# BreakoutBoard.net
KiCad netlist of a schematic drawn in EAGLE
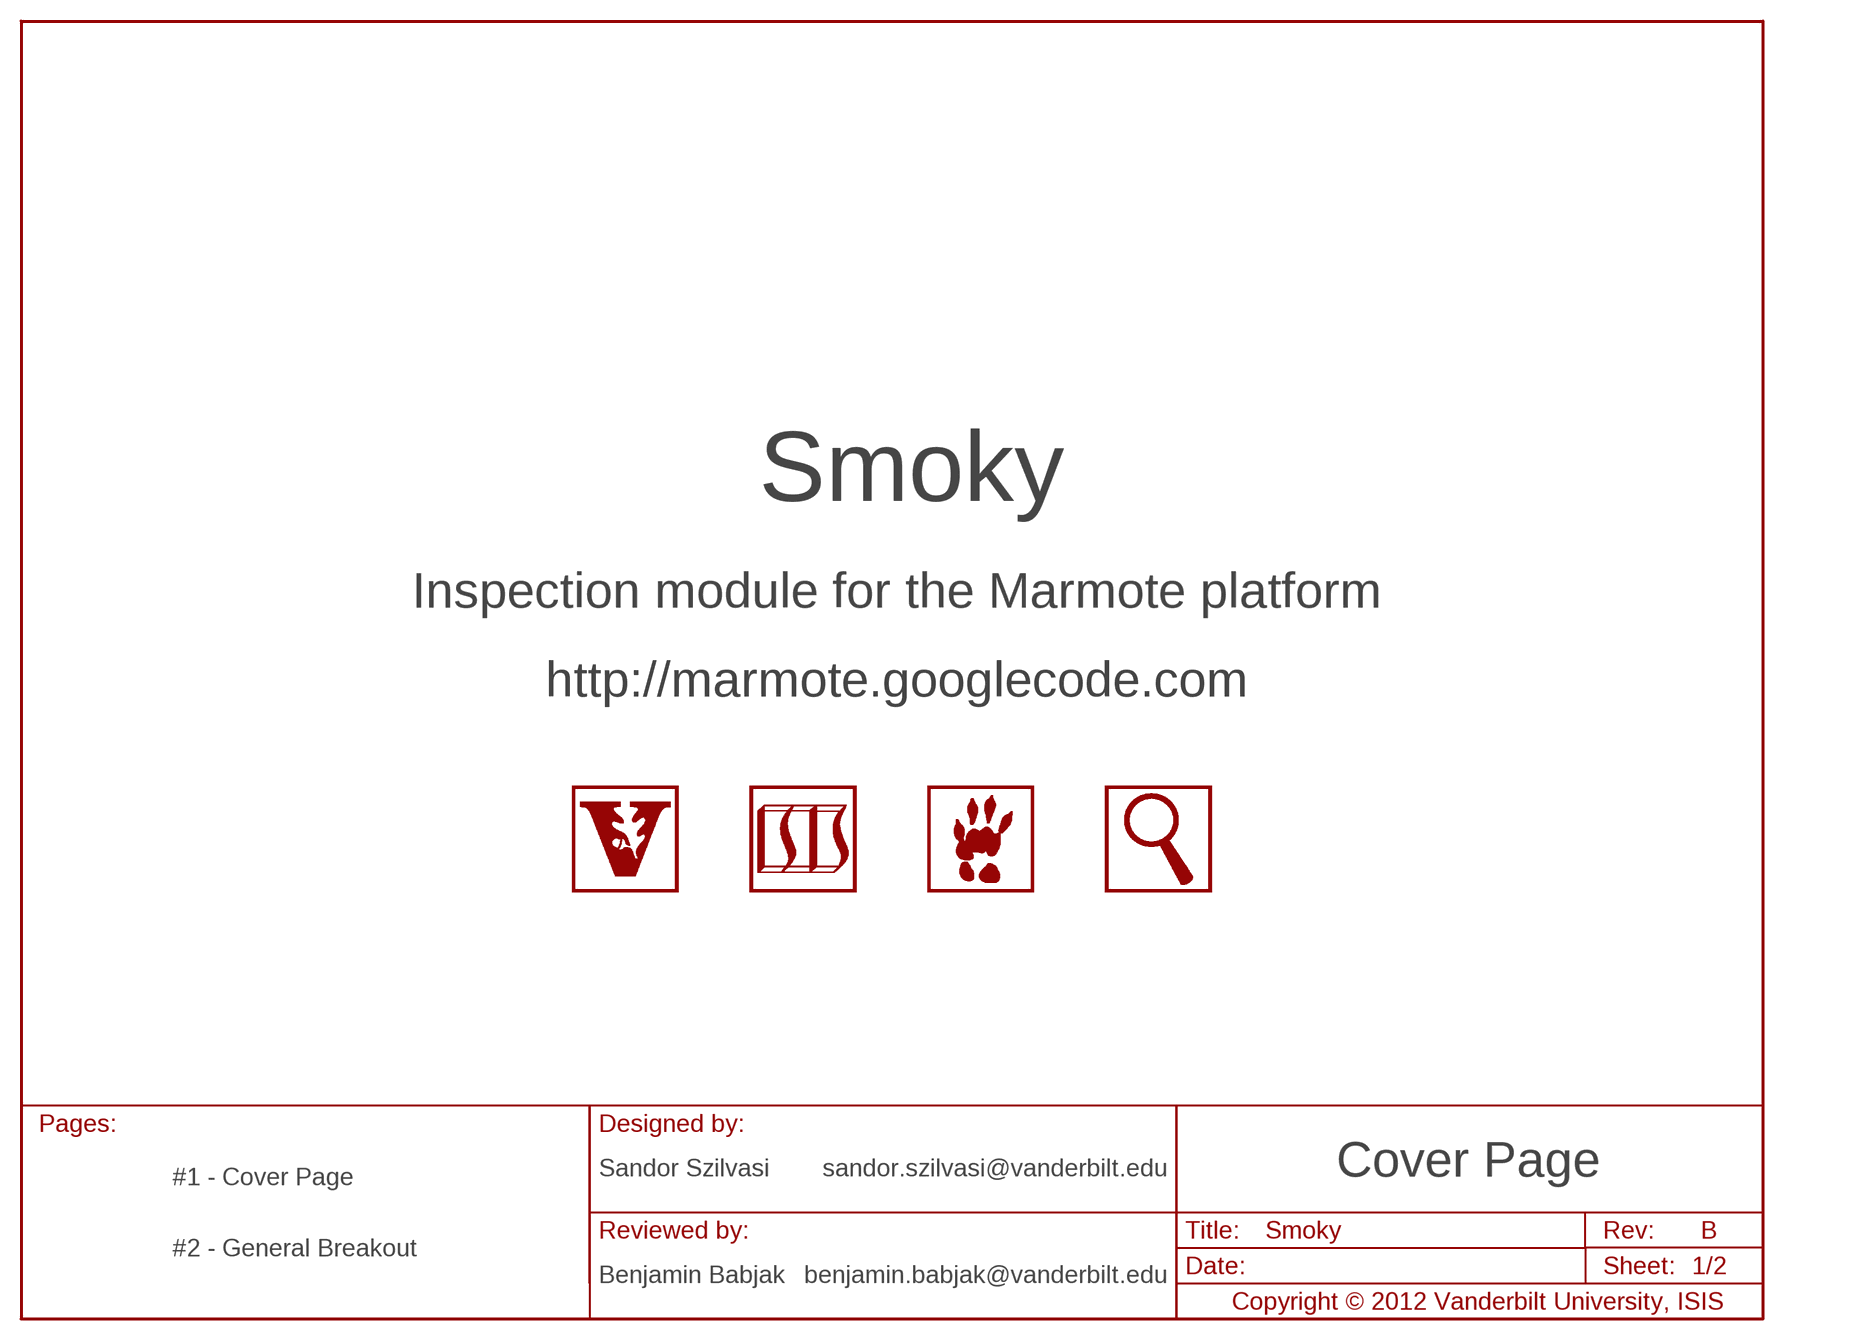
[diagram p0: schematic, sheet 1]
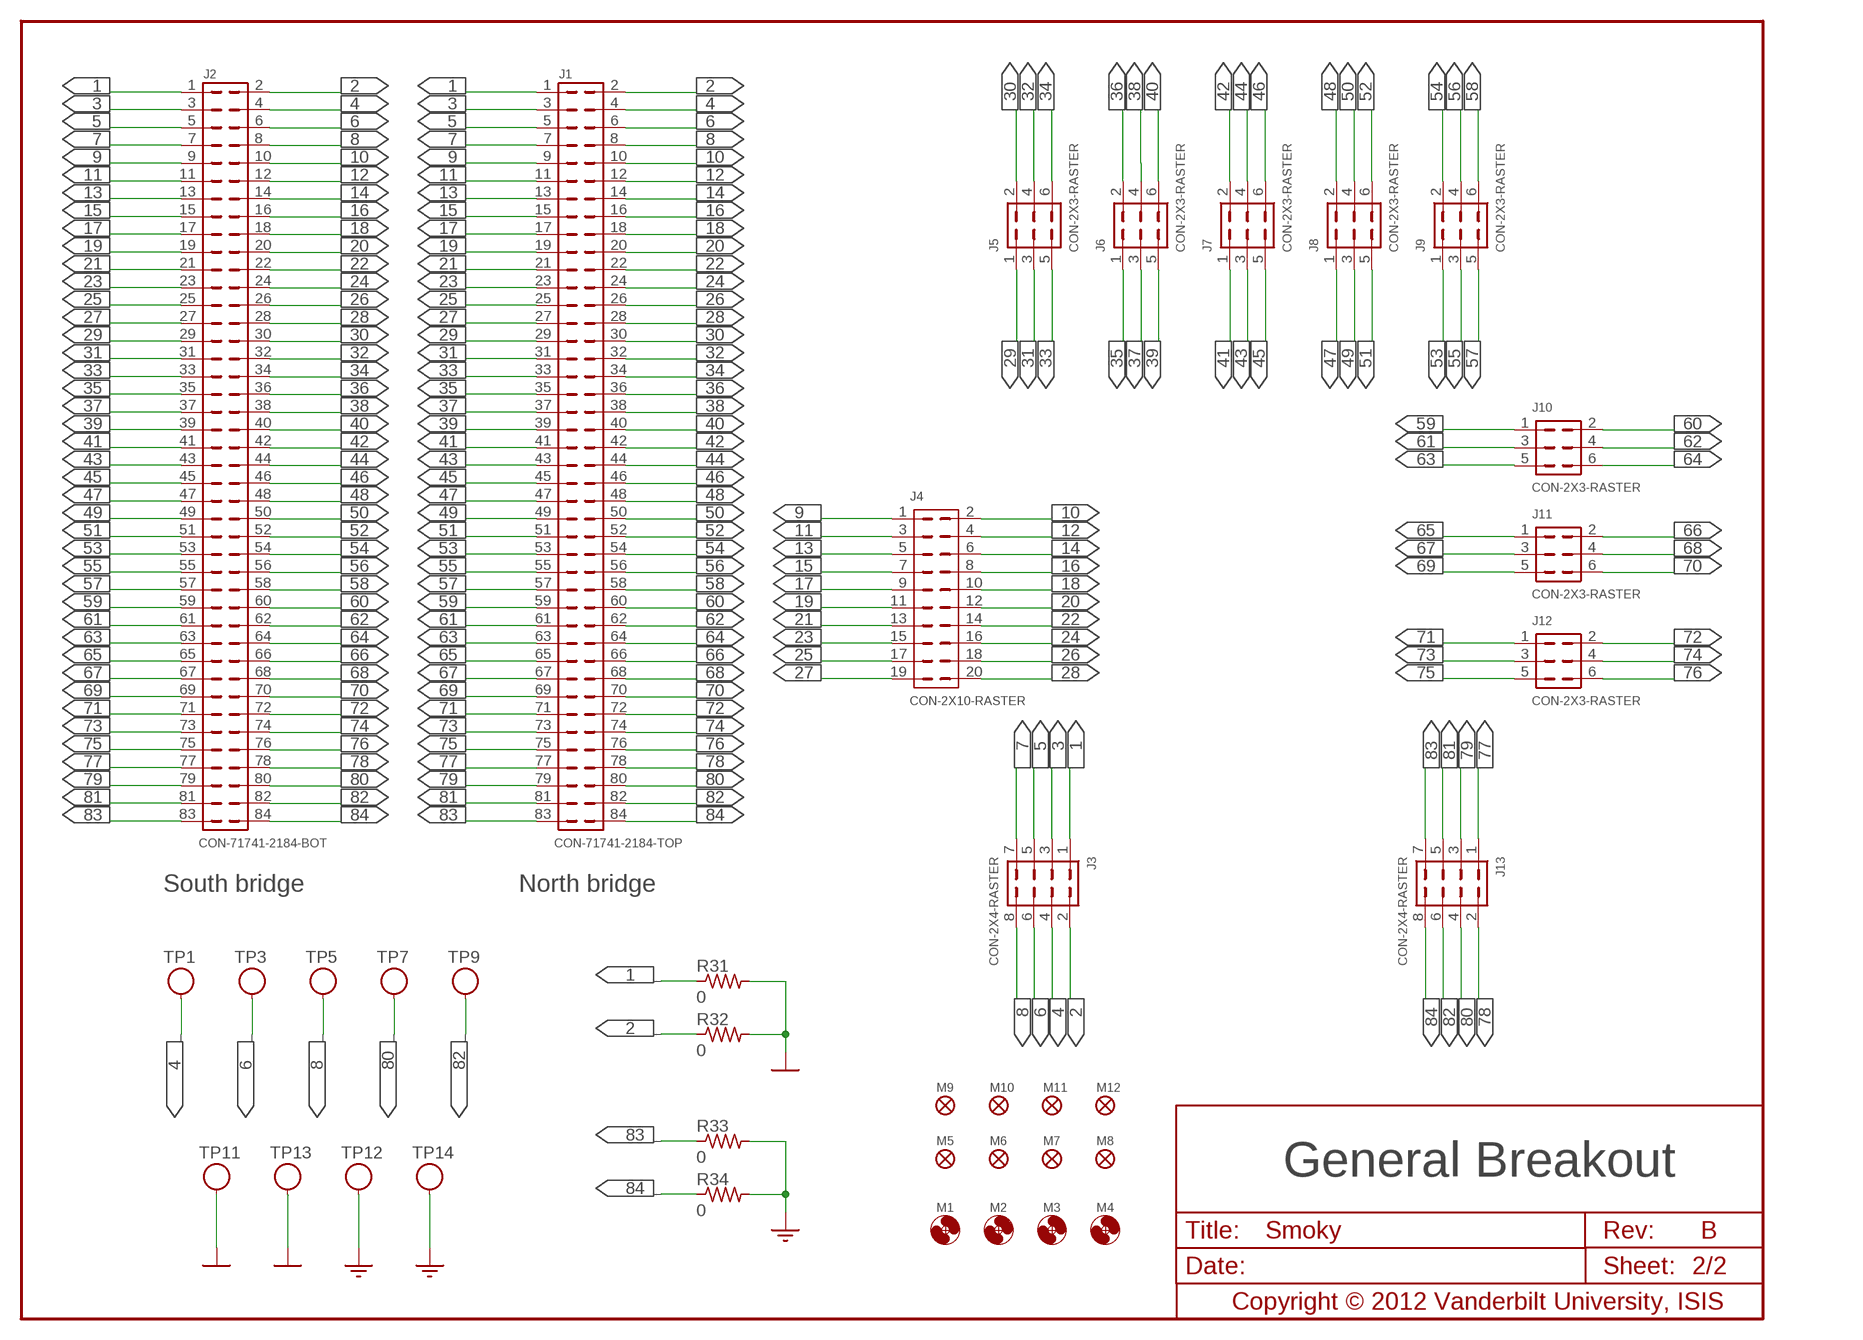
[diagram p1: schematic, sheet 2]

(export (version "E")
  (design (tool "Eeschema 10.0.6"))
  (components
    (comp (ref "J1")
      (value "CON-71741-2184-TOP")
      (footprint "eagle-import:71741-0002")
      (fields (field (name "MF") "Molex") (field (name "MPN") "71741-0002"))
      (libsource (lib "eagle-import") (part "CON-7174184-TOP-21"))
    )
    (comp (ref "J2")
      (value "CON-71741-2184-BOT")
      (footprint "eagle-import:71742-3003-BOT")
      (fields (field (name "MF") "Molex") (field (name "MPN") "71742-3003"))
      (libsource (lib "eagle-import") (part "CON-7174184-BOT-21"))
    )
    (comp (ref "J3")
      (value "CON-2X4-RASTER")
      (footprint "eagle-import:2X8")
      (libsource (lib "eagle-import") (part "CON-2X4-RASTER"))
    )
    (comp (ref "J4")
      (value "CON-2X10-RASTER")
      (footprint "eagle-import:2X20")
      (libsource (lib "eagle-import") (part "CON-2X10-RASTER"))
    )
    (comp (ref "J5")
      (value "CON-2X3-RASTER")
      (footprint "eagle-import:2X6")
      (libsource (lib "eagle-import") (part "CON-2X3-RASTER"))
    )
    (comp (ref "J6")
      (value "CON-2X3-RASTER")
      (footprint "eagle-import:2X6")
      (libsource (lib "eagle-import") (part "CON-2X3-RASTER"))
    )
    (comp (ref "J7")
      (value "CON-2X3-RASTER")
      (footprint "eagle-import:2X6")
      (libsource (lib "eagle-import") (part "CON-2X3-RASTER"))
    )
    (comp (ref "J8")
      (value "CON-2X3-RASTER")
      (footprint "eagle-import:2X6")
      (libsource (lib "eagle-import") (part "CON-2X3-RASTER"))
    )
    (comp (ref "J9")
      (value "CON-2X3-RASTER")
      (footprint "eagle-import:2X6")
      (libsource (lib "eagle-import") (part "CON-2X3-RASTER"))
    )
    (comp (ref "J10")
      (value "CON-2X3-RASTER")
      (footprint "eagle-import:2X6")
      (libsource (lib "eagle-import") (part "CON-2X3-RASTER"))
    )
    (comp (ref "J11")
      (value "CON-2X3-RASTER")
      (footprint "eagle-import:2X6")
      (libsource (lib "eagle-import") (part "CON-2X3-RASTER"))
    )
    (comp (ref "J12")
      (value "CON-2X3-RASTER")
      (footprint "eagle-import:2X6")
      (libsource (lib "eagle-import") (part "CON-2X3-RASTER"))
    )
    (comp (ref "J13")
      (value "CON-2X4-RASTER")
      (footprint "eagle-import:2X8")
      (libsource (lib "eagle-import") (part "CON-2X4-RASTER"))
    )
    (comp (ref "M1")
      (value "MOUNT-HOLE3.3")
      (footprint "eagle-import:3,3")
      (libsource (lib "eagle-import") (part "MOUNT-HOLE3.3"))
    )
    (comp (ref "M2")
      (value "MOUNT-HOLE3.3")
      (footprint "eagle-import:3,3")
      (libsource (lib "eagle-import") (part "MOUNT-HOLE3.3"))
    )
    (comp (ref "M3")
      (value "MOUNT-HOLE3.3")
      (footprint "eagle-import:3,3")
      (libsource (lib "eagle-import") (part "MOUNT-HOLE3.3"))
    )
    (comp (ref "M4")
      (value "MOUNT-HOLE3.3")
      (footprint "eagle-import:3,3")
      (libsource (lib "eagle-import") (part "MOUNT-HOLE3.3"))
    )
    (comp (ref "M5")
      (value "FIDUCIAL1X2")
      (footprint "eagle-import:FIDUCIAL-1X2")
      (libsource (lib "eagle-import") (part "FIDUCIAL1X2"))
    )
    (comp (ref "M6")
      (value "FIDUCIAL1X2")
      (footprint "eagle-import:FIDUCIAL-1X2")
      (libsource (lib "eagle-import") (part "FIDUCIAL1X2"))
    )
    (comp (ref "M7")
      (value "FIDUCIAL1X2")
      (footprint "eagle-import:FIDUCIAL-1X2")
      (libsource (lib "eagle-import") (part "FIDUCIAL1X2"))
    )
    (comp (ref "M8")
      (value "FIDUCIAL1X2")
      (footprint "eagle-import:FIDUCIAL-1X2")
      (libsource (lib "eagle-import") (part "FIDUCIAL1X2"))
    )
    (comp (ref "M9")
      (value "FIDUCIAL1X2")
      (footprint "eagle-import:FIDUCIAL-1X2")
      (libsource (lib "eagle-import") (part "FIDUCIAL1X2"))
    )
    (comp (ref "M10")
      (value "FIDUCIAL1X2")
      (footprint "eagle-import:FIDUCIAL-1X2")
      (libsource (lib "eagle-import") (part "FIDUCIAL1X2"))
    )
    (comp (ref "M11")
      (value "FIDUCIAL1X2")
      (footprint "eagle-import:FIDUCIAL-1X2")
      (libsource (lib "eagle-import") (part "FIDUCIAL1X2"))
    )
    (comp (ref "M12")
      (value "FIDUCIAL1X2")
      (footprint "eagle-import:FIDUCIAL-1X2")
      (libsource (lib "eagle-import") (part "FIDUCIAL1X2"))
    )
    (comp (ref "R31")
      (value "0")
      (footprint "eagle-import:R0805")
      (libsource (lib "eagle-import") (part "R0805"))
    )
    (comp (ref "R32")
      (value "0")
      (footprint "eagle-import:R0805")
      (libsource (lib "eagle-import") (part "R0805"))
    )
    (comp (ref "R33")
      (value "0")
      (footprint "eagle-import:R0805")
      (libsource (lib "eagle-import") (part "R0805"))
    )
    (comp (ref "R34")
      (value "0")
      (footprint "eagle-import:R0805")
      (libsource (lib "eagle-import") (part "R0805"))
    )
    (comp (ref "TP1")
      (value "TESTPOINT-BLUE")
      (footprint "eagle-import:TESTPOINT")
      (fields (field (name "MF") "Keystone") (field (name "MPN") "5122"))
      (libsource (lib "eagle-import") (part "TESTPOINT-BLUE"))
    )
    (comp (ref "TP3")
      (value "TESTPOINT-BLUE")
      (footprint "eagle-import:TESTPOINT")
      (fields (field (name "MF") "Keystone") (field (name "MPN") "5122"))
      (libsource (lib "eagle-import") (part "TESTPOINT-BLUE"))
    )
    (comp (ref "TP5")
      (value "TESTPOINT-BLUE")
      (footprint "eagle-import:TESTPOINT")
      (fields (field (name "MF") "Keystone") (field (name "MPN") "5122"))
      (libsource (lib "eagle-import") (part "TESTPOINT-BLUE"))
    )
    (comp (ref "TP7")
      (value "TESTPOINT-GREEN")
      (footprint "eagle-import:TESTPOINT")
      (fields (field (name "MF") "Keystone") (field (name "MPN") "5121"))
      (libsource (lib "eagle-import") (part "TESTPOINT-GREEN"))
    )
    (comp (ref "TP9")
      (value "TESTPOINT-GREEN")
      (footprint "eagle-import:TESTPOINT")
      (fields (field (name "MF") "Keystone") (field (name "MPN") "5121"))
      (libsource (lib "eagle-import") (part "TESTPOINT-GREEN"))
    )
    (comp (ref "TP11")
      (value "TESTPOINT-YELLOW")
      (footprint "eagle-import:TESTPOINT")
      (fields (field (name "MF") "Keystone") (field (name "MPN") "5009"))
      (libsource (lib "eagle-import") (part "TESTPOINT-YELLOW"))
    )
    (comp (ref "TP12")
      (value "TESTPOINT-YELLOW")
      (footprint "eagle-import:TESTPOINT")
      (fields (field (name "MF") "Keystone") (field (name "MPN") "5009"))
      (libsource (lib "eagle-import") (part "TESTPOINT-YELLOW"))
    )
    (comp (ref "TP13")
      (value "TESTPOINT-YELLOW")
      (footprint "eagle-import:TESTPOINT")
      (fields (field (name "MF") "Keystone") (field (name "MPN") "5009"))
      (libsource (lib "eagle-import") (part "TESTPOINT-YELLOW"))
    )
    (comp (ref "TP14")
      (value "TESTPOINT-YELLOW")
      (footprint "eagle-import:TESTPOINT")
      (fields (field (name "MF") "Keystone") (field (name "MPN") "5009"))
      (libsource (lib "eagle-import") (part "TESTPOINT-YELLOW"))
    )
    (comp (ref "LOGO1")
      (value "LOGO-MAGNIFYING-GLASS-600MIL-10MM-SS")
      (footprint "eagle-import:LOGO-MAGNIFYING-GLASS-10MM-SILKSCREEN")
      (libsource (lib "eagle-import") (part "LOGO-MAGNIFYING-GLASS-600MIL-10MM-SS"))
    )
    (comp (ref "LOGO5")
      (value "LOGO-VANDERBILT-600MIL-10MM-SS")
      (footprint "eagle-import:LOGO-VANDERBILT-10MM-SILKSCREEN")
      (libsource (lib "eagle-import") (part "LOGO-VANDERBILT-600MIL-10MM-SS"))
    )
    (comp (ref "LOGO6")
      (value "LOGO-ISIS-600MIL-10MM-SS")
      (footprint "eagle-import:LOGO-ISIS-10MM-SILKSCREEN")
      (libsource (lib "eagle-import") (part "LOGO-ISIS-600MIL-10MM-SS"))
    )
    (comp (ref "LOGO7")
      (value "LOGO-MARMOTE-600MIL-10MM-SS")
      (footprint "eagle-import:LOGO-MARMOTE-10MM-SILKSCREEN")
      (libsource (lib "eagle-import") (part "LOGO-MARMOTE-600MIL-10MM-SS"))
    )
  )
  (nets
    (net (code "1") (name "1") (class "Default")
      (node (ref "J1") (pin "1") (pinfunction "1_1") (pintype "passive"))
      (node (ref "J2") (pin "1") (pinfunction "1_1") (pintype "passive"))
      (node (ref "J3") (pin "1") (pinfunction "1_1") (pintype "passive"))
      (node (ref "R31") (pin "1") (pinfunction "1_1") (pintype "passive"))
    )
    (net (code "2") (name "2") (class "Default")
      (node (ref "J1") (pin "2") (pinfunction "2_2") (pintype "passive"))
      (node (ref "J2") (pin "2") (pinfunction "2_2") (pintype "passive"))
      (node (ref "J3") (pin "2") (pinfunction "2_2") (pintype "passive"))
      (node (ref "R32") (pin "1") (pinfunction "1_1") (pintype "passive"))
    )
    (net (code "3") (name "3") (class "Default")
      (node (ref "J1") (pin "3") (pinfunction "3_3") (pintype "passive"))
      (node (ref "J2") (pin "3") (pinfunction "3_3") (pintype "passive"))
      (node (ref "J3") (pin "3") (pinfunction "3_3") (pintype "passive"))
    )
    (net (code "4") (name "4") (class "Default")
      (node (ref "J1") (pin "4") (pinfunction "4_4") (pintype "passive"))
      (node (ref "J2") (pin "4") (pinfunction "4_4") (pintype "passive"))
      (node (ref "J3") (pin "4") (pinfunction "4_4") (pintype "passive"))
      (node (ref "TP1") (pin "1") (pinfunction "1_1") (pintype "power_in"))
    )
    (net (code "5") (name "5") (class "Default")
      (node (ref "J1") (pin "5") (pinfunction "5_5") (pintype "passive"))
      (node (ref "J2") (pin "5") (pinfunction "5_5") (pintype "passive"))
      (node (ref "J3") (pin "5") (pinfunction "5_5") (pintype "passive"))
    )
    (net (code "6") (name "6") (class "Default")
      (node (ref "J1") (pin "6") (pinfunction "6_6") (pintype "passive"))
      (node (ref "J2") (pin "6") (pinfunction "6_6") (pintype "passive"))
      (node (ref "J3") (pin "6") (pinfunction "6_6") (pintype "passive"))
      (node (ref "TP3") (pin "1") (pinfunction "1_1") (pintype "power_in"))
    )
    (net (code "7") (name "7") (class "Default")
      (node (ref "J1") (pin "7") (pinfunction "7_7") (pintype "passive"))
      (node (ref "J2") (pin "7") (pinfunction "7_7") (pintype "passive"))
      (node (ref "J3") (pin "7") (pinfunction "7_7") (pintype "passive"))
    )
    (net (code "8") (name "8") (class "Default")
      (node (ref "J1") (pin "8") (pinfunction "8_8") (pintype "passive"))
      (node (ref "J2") (pin "8") (pinfunction "8_8") (pintype "passive"))
      (node (ref "J3") (pin "8") (pinfunction "8_8") (pintype "passive"))
      (node (ref "TP5") (pin "1") (pinfunction "1_1") (pintype "power_in"))
    )
    (net (code "9") (name "9") (class "Default")
      (node (ref "J1") (pin "9") (pinfunction "9_9") (pintype "passive"))
      (node (ref "J2") (pin "9") (pinfunction "9_9") (pintype "passive"))
      (node (ref "J4") (pin "1") (pinfunction "1_1") (pintype "passive"))
    )
    (net (code "10") (name "10") (class "Default")
      (node (ref "J1") (pin "10") (pinfunction "10_10") (pintype "passive"))
      (node (ref "J2") (pin "10") (pinfunction "10_10") (pintype "passive"))
      (node (ref "J4") (pin "2") (pinfunction "2_2") (pintype "passive"))
    )
    (net (code "11") (name "11") (class "Default")
      (node (ref "J1") (pin "11") (pinfunction "11_11") (pintype "passive"))
      (node (ref "J2") (pin "11") (pinfunction "11_11") (pintype "passive"))
      (node (ref "J4") (pin "3") (pinfunction "3_3") (pintype "passive"))
    )
    (net (code "12") (name "12") (class "Default")
      (node (ref "J1") (pin "12") (pinfunction "12_12") (pintype "passive"))
      (node (ref "J2") (pin "12") (pinfunction "12_12") (pintype "passive"))
      (node (ref "J4") (pin "4") (pinfunction "4_4") (pintype "passive"))
    )
    (net (code "13") (name "13") (class "Default")
      (node (ref "J1") (pin "13") (pinfunction "13_13") (pintype "passive"))
      (node (ref "J2") (pin "13") (pinfunction "13_13") (pintype "passive"))
      (node (ref "J4") (pin "5") (pinfunction "5_5") (pintype "passive"))
    )
    (net (code "14") (name "14") (class "Default")
      (node (ref "J1") (pin "14") (pinfunction "14_14") (pintype "passive"))
      (node (ref "J2") (pin "14") (pinfunction "14_14") (pintype "passive"))
      (node (ref "J4") (pin "6") (pinfunction "6_6") (pintype "passive"))
    )
    (net (code "15") (name "15") (class "Default")
      (node (ref "J1") (pin "15") (pinfunction "15_15") (pintype "passive"))
      (node (ref "J2") (pin "15") (pinfunction "15_15") (pintype "passive"))
      (node (ref "J4") (pin "7") (pinfunction "7_7") (pintype "passive"))
    )
    (net (code "16") (name "16") (class "Default")
      (node (ref "J1") (pin "16") (pinfunction "16_16") (pintype "passive"))
      (node (ref "J2") (pin "16") (pinfunction "16_16") (pintype "passive"))
      (node (ref "J4") (pin "8") (pinfunction "8_8") (pintype "passive"))
    )
    (net (code "17") (name "17") (class "Default")
      (node (ref "J1") (pin "17") (pinfunction "17_17") (pintype "passive"))
      (node (ref "J2") (pin "17") (pinfunction "17_17") (pintype "passive"))
      (node (ref "J4") (pin "9") (pinfunction "9_9") (pintype "passive"))
    )
    (net (code "18") (name "18") (class "Default")
      (node (ref "J1") (pin "18") (pinfunction "18_18") (pintype "passive"))
      (node (ref "J2") (pin "18") (pinfunction "18_18") (pintype "passive"))
      (node (ref "J4") (pin "10") (pinfunction "10_10") (pintype "passive"))
    )
    (net (code "19") (name "19") (class "Default")
      (node (ref "J1") (pin "19") (pinfunction "19_19") (pintype "passive"))
      (node (ref "J2") (pin "19") (pinfunction "19_19") (pintype "passive"))
      (node (ref "J4") (pin "11") (pinfunction "11_11") (pintype "passive"))
    )
    (net (code "20") (name "20") (class "Default")
      (node (ref "J1") (pin "20") (pinfunction "20_20") (pintype "passive"))
      (node (ref "J2") (pin "20") (pinfunction "20_20") (pintype "passive"))
      (node (ref "J4") (pin "12") (pinfunction "12_12") (pintype "passive"))
    )
    (net (code "21") (name "21") (class "Default")
      (node (ref "J1") (pin "21") (pinfunction "21_21") (pintype "passive"))
      (node (ref "J2") (pin "21") (pinfunction "21_21") (pintype "passive"))
      (node (ref "J4") (pin "13") (pinfunction "13_13") (pintype "passive"))
    )
    (net (code "22") (name "22") (class "Default")
      (node (ref "J1") (pin "22") (pinfunction "22_22") (pintype "passive"))
      (node (ref "J2") (pin "22") (pinfunction "22_22") (pintype "passive"))
      (node (ref "J4") (pin "14") (pinfunction "14_14") (pintype "passive"))
    )
    (net (code "23") (name "23") (class "Default")
      (node (ref "J1") (pin "23") (pinfunction "23_23") (pintype "passive"))
      (node (ref "J2") (pin "23") (pinfunction "23_23") (pintype "passive"))
      (node (ref "J4") (pin "15") (pinfunction "15_15") (pintype "passive"))
    )
    (net (code "24") (name "24") (class "Default")
      (node (ref "J1") (pin "24") (pinfunction "24_24") (pintype "passive"))
      (node (ref "J2") (pin "24") (pinfunction "24_24") (pintype "passive"))
      (node (ref "J4") (pin "16") (pinfunction "16_16") (pintype "passive"))
    )
    (net (code "25") (name "25") (class "Default")
      (node (ref "J1") (pin "25") (pinfunction "25_25") (pintype "passive"))
      (node (ref "J2") (pin "25") (pinfunction "25_25") (pintype "passive"))
      (node (ref "J4") (pin "17") (pinfunction "17_17") (pintype "passive"))
    )
    (net (code "26") (name "26") (class "Default")
      (node (ref "J1") (pin "26") (pinfunction "26_26") (pintype "passive"))
      (node (ref "J2") (pin "26") (pinfunction "26_26") (pintype "passive"))
      (node (ref "J4") (pin "18") (pinfunction "18_18") (pintype "passive"))
    )
    (net (code "27") (name "27") (class "Default")
      (node (ref "J1") (pin "27") (pinfunction "27_27") (pintype "passive"))
      (node (ref "J2") (pin "27") (pinfunction "27_27") (pintype "passive"))
      (node (ref "J4") (pin "19") (pinfunction "19_19") (pintype "passive"))
    )
    (net (code "28") (name "28") (class "Default")
      (node (ref "J1") (pin "28") (pinfunction "28_28") (pintype "passive"))
      (node (ref "J2") (pin "28") (pinfunction "28_28") (pintype "passive"))
      (node (ref "J4") (pin "20") (pinfunction "20_20") (pintype "passive"))
    )
    (net (code "29") (name "29") (class "Default")
      (node (ref "J1") (pin "29") (pinfunction "29_29") (pintype "passive"))
      (node (ref "J2") (pin "29") (pinfunction "29_29") (pintype "passive"))
      (node (ref "J5") (pin "1") (pinfunction "1_1") (pintype "passive"))
    )
    (net (code "30") (name "30") (class "Default")
      (node (ref "J1") (pin "30") (pinfunction "30_30") (pintype "passive"))
      (node (ref "J2") (pin "30") (pinfunction "30_30") (pintype "passive"))
      (node (ref "J5") (pin "2") (pinfunction "2_2") (pintype "passive"))
    )
    (net (code "31") (name "31") (class "Default")
      (node (ref "J1") (pin "31") (pinfunction "31_31") (pintype "passive"))
      (node (ref "J2") (pin "31") (pinfunction "31_31") (pintype "passive"))
      (node (ref "J5") (pin "3") (pinfunction "3_3") (pintype "passive"))
    )
    (net (code "32") (name "32") (class "Default")
      (node (ref "J1") (pin "32") (pinfunction "32_32") (pintype "passive"))
      (node (ref "J2") (pin "32") (pinfunction "32_32") (pintype "passive"))
      (node (ref "J5") (pin "4") (pinfunction "4_4") (pintype "passive"))
    )
    (net (code "33") (name "33") (class "Default")
      (node (ref "J1") (pin "33") (pinfunction "33_33") (pintype "passive"))
      (node (ref "J2") (pin "33") (pinfunction "33_33") (pintype "passive"))
      (node (ref "J5") (pin "5") (pinfunction "5_5") (pintype "passive"))
    )
    (net (code "34") (name "34") (class "Default")
      (node (ref "J1") (pin "34") (pinfunction "34_34") (pintype "passive"))
      (node (ref "J2") (pin "34") (pinfunction "34_34") (pintype "passive"))
      (node (ref "J5") (pin "6") (pinfunction "6_6") (pintype "passive"))
    )
    (net (code "35") (name "35") (class "Default")
      (node (ref "J1") (pin "35") (pinfunction "35_35") (pintype "passive"))
      (node (ref "J2") (pin "35") (pinfunction "35_35") (pintype "passive"))
      (node (ref "J6") (pin "1") (pinfunction "1_1") (pintype "passive"))
    )
    (net (code "36") (name "36") (class "Default")
      (node (ref "J1") (pin "36") (pinfunction "36_36") (pintype "passive"))
      (node (ref "J2") (pin "36") (pinfunction "36_36") (pintype "passive"))
      (node (ref "J6") (pin "2") (pinfunction "2_2") (pintype "passive"))
    )
    (net (code "37") (name "37") (class "Default")
      (node (ref "J1") (pin "37") (pinfunction "37_37") (pintype "passive"))
      (node (ref "J2") (pin "37") (pinfunction "37_37") (pintype "passive"))
      (node (ref "J6") (pin "3") (pinfunction "3_3") (pintype "passive"))
    )
    (net (code "38") (name "38") (class "Default")
      (node (ref "J1") (pin "38") (pinfunction "38_38") (pintype "passive"))
      (node (ref "J2") (pin "38") (pinfunction "38_38") (pintype "passive"))
      (node (ref "J6") (pin "4") (pinfunction "4_4") (pintype "passive"))
    )
    (net (code "39") (name "39") (class "Default")
      (node (ref "J1") (pin "39") (pinfunction "39_39") (pintype "passive"))
      (node (ref "J2") (pin "39") (pinfunction "39_39") (pintype "passive"))
      (node (ref "J6") (pin "5") (pinfunction "5_5") (pintype "passive"))
    )
    (net (code "40") (name "40") (class "Default")
      (node (ref "J1") (pin "40") (pinfunction "40_40") (pintype "passive"))
      (node (ref "J2") (pin "40") (pinfunction "40_40") (pintype "passive"))
      (node (ref "J6") (pin "6") (pinfunction "6_6") (pintype "passive"))
    )
    (net (code "41") (name "41") (class "Default")
      (node (ref "J1") (pin "41") (pinfunction "41_41") (pintype "passive"))
      (node (ref "J2") (pin "41") (pinfunction "41_41") (pintype "passive"))
      (node (ref "J7") (pin "1") (pinfunction "1_1") (pintype "passive"))
    )
    (net (code "42") (name "42") (class "Default")
      (node (ref "J1") (pin "42") (pinfunction "42_42") (pintype "passive"))
      (node (ref "J2") (pin "42") (pinfunction "42_42") (pintype "passive"))
      (node (ref "J7") (pin "2") (pinfunction "2_2") (pintype "passive"))
    )
    (net (code "43") (name "43") (class "Default")
      (node (ref "J1") (pin "43") (pinfunction "43_43") (pintype "passive"))
      (node (ref "J2") (pin "43") (pinfunction "43_43") (pintype "passive"))
      (node (ref "J7") (pin "3") (pinfunction "3_3") (pintype "passive"))
    )
    (net (code "44") (name "44") (class "Default")
      (node (ref "J1") (pin "44") (pinfunction "44_44") (pintype "passive"))
      (node (ref "J2") (pin "44") (pinfunction "44_44") (pintype "passive"))
      (node (ref "J7") (pin "4") (pinfunction "4_4") (pintype "passive"))
    )
    (net (code "45") (name "45") (class "Default")
      (node (ref "J1") (pin "45") (pinfunction "45_45") (pintype "passive"))
      (node (ref "J2") (pin "45") (pinfunction "45_45") (pintype "passive"))
      (node (ref "J7") (pin "5") (pinfunction "5_5") (pintype "passive"))
    )
    (net (code "46") (name "46") (class "Default")
      (node (ref "J1") (pin "46") (pinfunction "46_46") (pintype "passive"))
      (node (ref "J2") (pin "46") (pinfunction "46_46") (pintype "passive"))
      (node (ref "J7") (pin "6") (pinfunction "6_6") (pintype "passive"))
    )
    (net (code "47") (name "47") (class "Default")
      (node (ref "J1") (pin "47") (pinfunction "47_47") (pintype "passive"))
      (node (ref "J2") (pin "47") (pinfunction "47_47") (pintype "passive"))
      (node (ref "J8") (pin "1") (pinfunction "1_1") (pintype "passive"))
    )
    (net (code "48") (name "48") (class "Default")
      (node (ref "J1") (pin "48") (pinfunction "48_48") (pintype "passive"))
      (node (ref "J2") (pin "48") (pinfunction "48_48") (pintype "passive"))
      (node (ref "J8") (pin "2") (pinfunction "2_2") (pintype "passive"))
    )
    (net (code "49") (name "49") (class "Default")
      (node (ref "J1") (pin "49") (pinfunction "49_49") (pintype "passive"))
      (node (ref "J2") (pin "49") (pinfunction "49_49") (pintype "passive"))
      (node (ref "J8") (pin "3") (pinfunction "3_3") (pintype "passive"))
    )
    (net (code "50") (name "50") (class "Default")
      (node (ref "J1") (pin "50") (pinfunction "50_50") (pintype "passive"))
      (node (ref "J2") (pin "50") (pinfunction "50_50") (pintype "passive"))
      (node (ref "J8") (pin "4") (pinfunction "4_4") (pintype "passive"))
    )
    (net (code "51") (name "51") (class "Default")
      (node (ref "J1") (pin "51") (pinfunction "51_51") (pintype "passive"))
      (node (ref "J2") (pin "51") (pinfunction "51_51") (pintype "passive"))
      (node (ref "J8") (pin "5") (pinfunction "5_5") (pintype "passive"))
    )
    (net (code "52") (name "52") (class "Default")
      (node (ref "J1") (pin "52") (pinfunction "52_52") (pintype "passive"))
      (node (ref "J2") (pin "52") (pinfunction "52_52") (pintype "passive"))
      (node (ref "J8") (pin "6") (pinfunction "6_6") (pintype "passive"))
    )
    (net (code "53") (name "53") (class "Default")
      (node (ref "J1") (pin "53") (pinfunction "53_53") (pintype "passive"))
      (node (ref "J2") (pin "53") (pinfunction "53_53") (pintype "passive"))
      (node (ref "J9") (pin "1") (pinfunction "1_1") (pintype "passive"))
    )
    (net (code "54") (name "54") (class "Default")
      (node (ref "J1") (pin "54") (pinfunction "54_54") (pintype "passive"))
      (node (ref "J2") (pin "54") (pinfunction "54_54") (pintype "passive"))
      (node (ref "J9") (pin "2") (pinfunction "2_2") (pintype "passive"))
    )
    (net (code "55") (name "55") (class "Default")
      (node (ref "J1") (pin "55") (pinfunction "55_55") (pintype "passive"))
      (node (ref "J2") (pin "55") (pinfunction "55_55") (pintype "passive"))
      (node (ref "J9") (pin "3") (pinfunction "3_3") (pintype "passive"))
    )
    (net (code "56") (name "56") (class "Default")
      (node (ref "J1") (pin "56") (pinfunction "56_56") (pintype "passive"))
      (node (ref "J2") (pin "56") (pinfunction "56_56") (pintype "passive"))
      (node (ref "J9") (pin "4") (pinfunction "4_4") (pintype "passive"))
    )
    (net (code "57") (name "57") (class "Default")
      (node (ref "J1") (pin "57") (pinfunction "57_57") (pintype "passive"))
      (node (ref "J2") (pin "57") (pinfunction "57_57") (pintype "passive"))
      (node (ref "J9") (pin "5") (pinfunction "5_5") (pintype "passive"))
    )
    (net (code "58") (name "58") (class "Default")
      (node (ref "J1") (pin "58") (pinfunction "58_58") (pintype "passive"))
      (node (ref "J2") (pin "58") (pinfunction "58_58") (pintype "passive"))
      (node (ref "J9") (pin "6") (pinfunction "6_6") (pintype "passive"))
    )
    (net (code "59") (name "59") (class "Default")
      (node (ref "J1") (pin "59") (pinfunction "59_59") (pintype "passive"))
      (node (ref "J10") (pin "1") (pinfunction "1_1") (pintype "passive"))
      (node (ref "J2") (pin "59") (pinfunction "59_59") (pintype "passive"))
    )
    (net (code "60") (name "60") (class "Default")
      (node (ref "J1") (pin "60") (pinfunction "60_60") (pintype "passive"))
      (node (ref "J10") (pin "2") (pinfunction "2_2") (pintype "passive"))
      (node (ref "J2") (pin "60") (pinfunction "60_60") (pintype "passive"))
    )
    (net (code "61") (name "61") (class "Default")
      (node (ref "J1") (pin "61") (pinfunction "61_61") (pintype "passive"))
      (node (ref "J10") (pin "3") (pinfunction "3_3") (pintype "passive"))
      (node (ref "J2") (pin "61") (pinfunction "61_61") (pintype "passive"))
    )
    (net (code "62") (name "62") (class "Default")
      (node (ref "J1") (pin "62") (pinfunction "62_62") (pintype "passive"))
      (node (ref "J10") (pin "4") (pinfunction "4_4") (pintype "passive"))
      (node (ref "J2") (pin "62") (pinfunction "62_62") (pintype "passive"))
    )
    (net (code "63") (name "63") (class "Default")
      (node (ref "J1") (pin "63") (pinfunction "63_63") (pintype "passive"))
      (node (ref "J10") (pin "5") (pinfunction "5_5") (pintype "passive"))
      (node (ref "J2") (pin "63") (pinfunction "63_63") (pintype "passive"))
    )
    (net (code "64") (name "64") (class "Default")
      (node (ref "J1") (pin "64") (pinfunction "64_64") (pintype "passive"))
      (node (ref "J10") (pin "6") (pinfunction "6_6") (pintype "passive"))
      (node (ref "J2") (pin "64") (pinfunction "64_64") (pintype "passive"))
    )
    (net (code "65") (name "65") (class "Default")
      (node (ref "J1") (pin "65") (pinfunction "65_65") (pintype "passive"))
      (node (ref "J11") (pin "1") (pinfunction "1_1") (pintype "passive"))
      (node (ref "J2") (pin "65") (pinfunction "65_65") (pintype "passive"))
    )
    (net (code "66") (name "66") (class "Default")
      (node (ref "J1") (pin "66") (pinfunction "66_66") (pintype "passive"))
      (node (ref "J11") (pin "2") (pinfunction "2_2") (pintype "passive"))
      (node (ref "J2") (pin "66") (pinfunction "66_66") (pintype "passive"))
    )
    (net (code "67") (name "67") (class "Default")
      (node (ref "J1") (pin "67") (pinfunction "67_67") (pintype "passive"))
      (node (ref "J11") (pin "3") (pinfunction "3_3") (pintype "passive"))
      (node (ref "J2") (pin "67") (pinfunction "67_67") (pintype "passive"))
    )
    (net (code "68") (name "68") (class "Default")
      (node (ref "J1") (pin "68") (pinfunction "68_68") (pintype "passive"))
      (node (ref "J11") (pin "4") (pinfunction "4_4") (pintype "passive"))
      (node (ref "J2") (pin "68") (pinfunction "68_68") (pintype "passive"))
    )
    (net (code "69") (name "69") (class "Default")
      (node (ref "J1") (pin "69") (pinfunction "69_69") (pintype "passive"))
      (node (ref "J11") (pin "5") (pinfunction "5_5") (pintype "passive"))
      (node (ref "J2") (pin "69") (pinfunction "69_69") (pintype "passive"))
    )
    (net (code "70") (name "70") (class "Default")
      (node (ref "J1") (pin "70") (pinfunction "70_70") (pintype "passive"))
      (node (ref "J11") (pin "6") (pinfunction "6_6") (pintype "passive"))
      (node (ref "J2") (pin "70") (pinfunction "70_70") (pintype "passive"))
    )
    (net (code "71") (name "71") (class "Default")
      (node (ref "J1") (pin "71") (pinfunction "71_71") (pintype "passive"))
      (node (ref "J12") (pin "1") (pinfunction "1_1") (pintype "passive"))
      (node (ref "J2") (pin "71") (pinfunction "71_71") (pintype "passive"))
    )
    (net (code "72") (name "72") (class "Default")
      (node (ref "J1") (pin "72") (pinfunction "72_72") (pintype "passive"))
      (node (ref "J12") (pin "2") (pinfunction "2_2") (pintype "passive"))
      (node (ref "J2") (pin "72") (pinfunction "72_72") (pintype "passive"))
    )
    (net (code "73") (name "73") (class "Default")
      (node (ref "J1") (pin "73") (pinfunction "73_73") (pintype "passive"))
      (node (ref "J12") (pin "3") (pinfunction "3_3") (pintype "passive"))
      (node (ref "J2") (pin "73") (pinfunction "73_73") (pintype "passive"))
    )
    (net (code "74") (name "74") (class "Default")
      (node (ref "J1") (pin "74") (pinfunction "74_74") (pintype "passive"))
      (node (ref "J12") (pin "4") (pinfunction "4_4") (pintype "passive"))
      (node (ref "J2") (pin "74") (pinfunction "74_74") (pintype "passive"))
    )
    (net (code "75") (name "75") (class "Default")
      (node (ref "J1") (pin "75") (pinfunction "75_75") (pintype "passive"))
      (node (ref "J12") (pin "5") (pinfunction "5_5") (pintype "passive"))
      (node (ref "J2") (pin "75") (pinfunction "75_75") (pintype "passive"))
    )
    (net (code "76") (name "76") (class "Default")
      (node (ref "J1") (pin "76") (pinfunction "76_76") (pintype "passive"))
      (node (ref "J12") (pin "6") (pinfunction "6_6") (pintype "passive"))
      (node (ref "J2") (pin "76") (pinfunction "76_76") (pintype "passive"))
    )
    (net (code "77") (name "77") (class "Default")
      (node (ref "J1") (pin "77") (pinfunction "77_77") (pintype "passive"))
      (node (ref "J13") (pin "1") (pinfunction "1_1") (pintype "passive"))
      (node (ref "J2") (pin "77") (pinfunction "77_77") (pintype "passive"))
    )
    (net (code "78") (name "78") (class "Default")
      (node (ref "J1") (pin "78") (pinfunction "78_78") (pintype "passive"))
      (node (ref "J13") (pin "2") (pinfunction "2_2") (pintype "passive"))
      (node (ref "J2") (pin "78") (pinfunction "78_78") (pintype "passive"))
    )
    (net (code "79") (name "79") (class "Default")
      (node (ref "J1") (pin "79") (pinfunction "79_79") (pintype "passive"))
      (node (ref "J13") (pin "3") (pinfunction "3_3") (pintype "passive"))
      (node (ref "J2") (pin "79") (pinfunction "79_79") (pintype "passive"))
    )
    (net (code "80") (name "80") (class "Default")
      (node (ref "J1") (pin "80") (pinfunction "80_80") (pintype "passive"))
      (node (ref "J13") (pin "4") (pinfunction "4_4") (pintype "passive"))
      (node (ref "J2") (pin "80") (pinfunction "80_80") (pintype "passive"))
      (node (ref "TP7") (pin "1") (pinfunction "1_1") (pintype "power_in"))
    )
    (net (code "81") (name "81") (class "Default")
      (node (ref "J1") (pin "81") (pinfunction "81_81") (pintype "passive"))
      (node (ref "J13") (pin "5") (pinfunction "5_5") (pintype "passive"))
      (node (ref "J2") (pin "81") (pinfunction "81_81") (pintype "passive"))
    )
    (net (code "82") (name "82") (class "Default")
      (node (ref "J1") (pin "82") (pinfunction "82_82") (pintype "passive"))
      (node (ref "J13") (pin "6") (pinfunction "6_6") (pintype "passive"))
      (node (ref "J2") (pin "82") (pinfunction "82_82") (pintype "passive"))
      (node (ref "TP9") (pin "1") (pinfunction "1_1") (pintype "power_in"))
    )
    (net (code "83") (name "83") (class "Default")
      (node (ref "J1") (pin "83") (pinfunction "83_83") (pintype "passive"))
      (node (ref "J13") (pin "7") (pinfunction "7_7") (pintype "passive"))
      (node (ref "J2") (pin "83") (pinfunction "83_83") (pintype "passive"))
      (node (ref "R33") (pin "1") (pinfunction "1_1") (pintype "passive"))
    )
    (net (code "84") (name "84") (class "Default")
      (node (ref "J1") (pin "84") (pinfunction "84_84") (pintype "passive"))
      (node (ref "J13") (pin "8") (pinfunction "8_8") (pintype "passive"))
      (node (ref "J2") (pin "84") (pinfunction "84_84") (pintype "passive"))
      (node (ref "R34") (pin "1") (pinfunction "1_1") (pintype "passive"))
    )
    (net (code "85") (name "AGND") (class "Default")
      (node (ref "R33") (pin "2") (pinfunction "2_2") (pintype "passive"))
      (node (ref "R34") (pin "2") (pinfunction "2_2") (pintype "passive"))
      (node (ref "TP12") (pin "1") (pinfunction "1_1") (pintype "power_in"))
      (node (ref "TP14") (pin "1") (pinfunction "1_1") (pintype "power_in"))
    )
    (net (code "86") (name "DGND") (class "Default")
      (node (ref "R31") (pin "2") (pinfunction "2_2") (pintype "passive"))
      (node (ref "R32") (pin "2") (pinfunction "2_2") (pintype "passive"))
      (node (ref "TP11") (pin "1") (pinfunction "1_1") (pintype "power_in"))
      (node (ref "TP13") (pin "1") (pinfunction "1_1") (pintype "power_in"))
    )
  )
)
